# MCU_NODE.net
KiCad netlist of a schematic drawn in Altium Designer
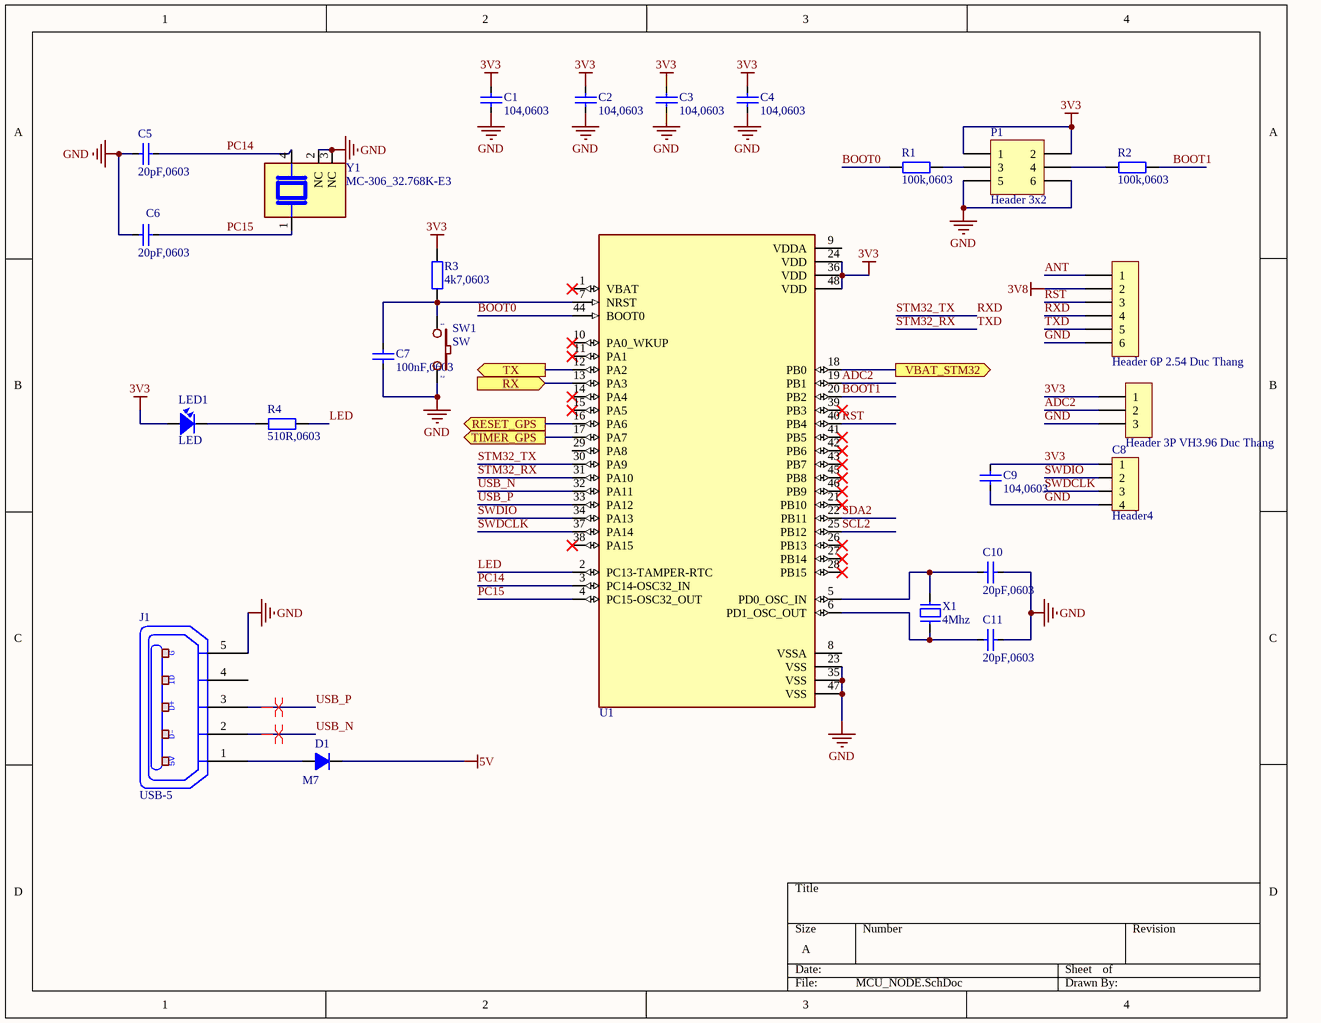
[diagram p0: MCU_NODE.SchDoc]

(export (version "E")
  (design (tool "Eeschema 10.0.6"))
  (components
    (comp (ref "C1")
      (value "104,0603")
      (footprint "CAP_0603")
      (description "Capacitor")
      (fields (field (name "PUBLISHER") "Altium Limited"))
      (libsource (lib "My Library") (part "CapSMD"))
    )
    (comp (ref "C2")
      (value "104,0603")
      (footprint "CAP_0603")
      (description "Capacitor")
      (fields (field (name "PUBLISHER") "Altium Limited"))
      (libsource (lib "My Library") (part "CapSMD"))
    )
    (comp (ref "C3")
      (value "104,0603")
      (footprint "CAP_0603")
      (description "Capacitor")
      (fields (field (name "PUBLISHER") "Altium Limited"))
      (libsource (lib "My Library") (part "CapSMD"))
    )
    (comp (ref "C4")
      (value "104,0603")
      (footprint "CAP_0603")
      (description "Capacitor")
      (fields (field (name "PUBLISHER") "Altium Limited"))
      (libsource (lib "My Library") (part "CapSMD"))
    )
    (comp (ref "C5")
      (value "20pF,0603")
      (footprint "CAP_0603")
      (description "Capacitor")
      (fields (field (name "PUBLISHER") "Altium Limited"))
      (libsource (lib "My Library") (part "CapSMD"))
    )
    (comp (ref "C6")
      (value "20pF,0603")
      (footprint "CAP_0603")
      (description "Capacitor")
      (fields (field (name "PUBLISHER") "Altium Limited"))
      (libsource (lib "My Library") (part "CapSMD"))
    )
    (comp (ref "C7")
      (value "100nF,0603")
      (footprint "CAP_0603")
      (description "Capacitor")
      (fields (field (name "PUBLISHER") "Altium Limited"))
      (libsource (lib "My Library") (part "CapSMD"))
    )
    (comp (ref "C8")
      (value "Header4")
      (footprint "JP4-D1C")
      (description "Header IDC, 4 x 1 Pin Vertical 2.54mm Pitch (Non-Boxed, Male)")
      (fields
        (field (name "MANUFACTURER") "Würth Elektronik eiSos GmbH")
        (field (name "PARTNO") "613002143121")
        (field (name "CREATED BY") "Karrer Zheng")
      )
      (libsource (lib "My Library") (part "Header4"))
    )
    (comp (ref "C9")
      (value "104,0603")
      (footprint "CAP_0603")
      (description "Capacitor")
      (fields (field (name "PUBLISHER") "Altium Limited"))
      (libsource (lib "My Library") (part "CapSMD"))
    )
    (comp (ref "C10")
      (value "20pF,0603")
      (footprint "CAP_0603")
      (description "Capacitor")
      (fields (field (name "PUBLISHER") "Altium Limited"))
      (libsource (lib "My Library") (part "CapSMD"))
    )
    (comp (ref "C11")
      (value "20pF,0603")
      (footprint "CAP_0603")
      (description "Capacitor")
      (fields (field (name "PUBLISHER") "Altium Limited"))
      (libsource (lib "My Library") (part "CapSMD"))
    )
    (comp (ref "D1")
      (value "M7")
      (footprint "SMA")
      (description "Diode 1A")
      (libsource (lib "Main") (part "D1A"))
    )
    (comp (ref "H1")
      (value "Header 6P 2.54 Duc Thang")
      (footprint "XH2.54M-6")
      (description "Cắm")
      (libsource (lib "Header") (part "Header 6P 2.54 Duc Thang"))
    )
    (comp (ref "H2")
      (value "Header 3P VH3.96 Duc Thang")
      (footprint "VH3.96M-3")
      (description "Cắm")
      (libsource (lib "Header") (part "Header 3P VH3.96 Duc Thang"))
    )
    (comp (ref "J1")
      (value "USB-5")
      (footprint "USB-M1")
      (fields
        (field (name "MANUFACTURER") "FCI")
        (field (name "MANUFACTURER PART NUMBER") "10118193-0001LF")
        (field (name ".CREATOR") "MM")
        (field (name ".CHECKED PCB") "RF")
        (field (name ".CHECKED SCH") "MM")
      )
      (libsource (lib "My Library") (part "USB-5"))
    )
    (comp (ref "LED1")
      (value "LED")
      (footprint "LED-0805-Blue")
      (description "LED Single colour Green and Red")
      (libsource (lib "My Library") (part "LED"))
    )
    (comp (ref "P1")
      (value "Header 3x2")
      (footprint "Header 3x2")
      (description "Header, 6-Pin, 2-Row")
      (fields (field (name "PUBLISHER") "Altium Limited"))
      (libsource (lib "hphonglib") (part "Header 3x2"))
    )
    (comp (ref "R1")
      (value "100k,0603")
      (footprint "RES-SMD-0603")
      (description "Resistor SMD")
      (fields
        (field (name "MANUFACTURER") "Generic Components")
        (field (name "PUBLISHER") "Altium Hobart Technology Centre")
      )
      (libsource (lib "My Library") (part "Resistor - SMD"))
    )
    (comp (ref "R2")
      (value "100k,0603")
      (footprint "RES-SMD-0603")
      (description "Resistor SMD")
      (fields
        (field (name "MANUFACTURER") "Generic Components")
        (field (name "PUBLISHER") "Altium Hobart Technology Centre")
      )
      (libsource (lib "My Library") (part "Resistor - SMD"))
    )
    (comp (ref "R3")
      (value "4k7,0603")
      (footprint "RES-SMD-0603")
      (description "Resistor SMD")
      (fields
        (field (name "MANUFACTURER") "Generic Components")
        (field (name "PUBLISHER") "Altium Hobart Technology Centre")
      )
      (libsource (lib "My Library") (part "Resistor - SMD"))
    )
    (comp (ref "R4")
      (value "510R,0603")
      (footprint "RES-SMD-0603")
      (description "Resistor SMD")
      (fields
        (field (name "MANUFACTURER") "Generic Components")
        (field (name "PUBLISHER") "Altium Hobart Technology Centre")
      )
      (libsource (lib "My Library") (part "Resistor - SMD"))
    )
    (comp (ref "SW1")
      (value "SW")
      (footprint "SW-SMD")
      (description "Switch button 2 pin")
      (libsource (lib "My Library") (part "SW2"))
    )
    (comp (ref "U1")
      (value "STM32")
      (footprint "LQFP 48")
      (description "STM32 ARM-based 32-bit MCU with 64 Kbytes Flash, 64-pin LQFP, Industrial Temperature")
      (libsource (lib "My Library") (part "STM32F103C8T6"))
    )
    (comp (ref "X1")
      (value "4Mhz")
      (footprint "XT2")
      (description "Crystal For all Crystal 2pin.")
      (libsource (lib "My Library") (part "XT2"))
    )
    (comp (ref "Y1")
      (value "MC-306_32.768K-E3")
      (footprint "XTAL_MC-306_32.768K-E3")
      (description "CRYSTAL 32.7680KHZ 6PF SMD")
      (fields (field (name "MF") "EPSON") (field (name "MP") "MC-306 32.768K-E3"))
      (libsource (lib "MC-306_32.768K-E3") (part "MC-306_32.768K-E3"))
    )
  )
  (nets
    (net (code "1") (name "/ADC2") (class "Default")
      (node (ref "H2") (pin "2") (pinfunction "2_2") (pintype "passive"))
      (node (ref "U1") (pin "19") (pinfunction "PB1_19") (pintype "bidirectional"))
    )
    (net (code "2") (name "/ANT") (class "Default")
      (node (ref "H1") (pin "1") (pinfunction "1_1") (pintype "passive"))
    )
    (net (code "3") (name "/BOOT0") (class "Default")
      (node (ref "R1") (pin "1") (pinfunction "1_1") (pintype "passive"))
      (node (ref "U1") (pin "44") (pinfunction "BOOT0_44") (pintype "input"))
    )
    (net (code "4") (name "/BOOT1") (class "Default")
      (node (ref "R2") (pin "2") (pinfunction "2_2") (pintype "passive"))
      (node (ref "U1") (pin "20") (pinfunction "PB2_20") (pintype "bidirectional"))
    )
    (net (code "5") (name "/LED") (class "Default")
      (node (ref "R4") (pin "2") (pinfunction "2_2") (pintype "passive"))
      (node (ref "U1") (pin "2") (pinfunction "PC13-TAMPER-RTC_2") (pintype "bidirectional"))
    )
    (net (code "6") (name "/PC14") (class "Default")
      (node (ref "C5") (pin "2") (pinfunction "2_2") (pintype "passive"))
      (node (ref "U1") (pin "3") (pinfunction "PC14-OSC32_IN_3") (pintype "bidirectional"))
      (node (ref "Y1") (pin "4") (pinfunction "2_4") (pintype "passive"))
    )
    (net (code "7") (name "/PC15") (class "Default")
      (node (ref "C6") (pin "2") (pinfunction "2_2") (pintype "passive"))
      (node (ref "U1") (pin "4") (pinfunction "PC15-OSC32_OUT_4") (pintype "bidirectional"))
      (node (ref "Y1") (pin "1") (pinfunction "1_1") (pintype "passive"))
    )
    (net (code "8") (name "/RESET_GPS") (class "Default")
      (node (ref "U1") (pin "16") (pinfunction "PA6_16") (pintype "bidirectional"))
    )
    (net (code "9") (name "/RST") (class "Default")
      (node (ref "H1") (pin "3") (pinfunction "3_3") (pintype "passive"))
      (node (ref "U1") (pin "40") (pinfunction "PB4_40") (pintype "bidirectional"))
    )
    (net (code "10") (name "/RX") (class "Default")
      (node (ref "U1") (pin "13") (pinfunction "PA3_13") (pintype "bidirectional"))
    )
    (net (code "11") (name "/RXD") (class "Default")
      (node (ref "H1") (pin "4") (pinfunction "4_4") (pintype "passive"))
      (node (ref "U1") (pin "30") (pinfunction "PA9_30") (pintype "bidirectional"))
    )
    (net (code "12") (name "/SCL2") (class "Default")
      (node (ref "U1") (pin "25") (pinfunction "PB12_25") (pintype "bidirectional"))
    )
    (net (code "13") (name "/SDA2") (class "Default")
      (node (ref "U1") (pin "22") (pinfunction "PB11_22") (pintype "bidirectional"))
    )
    (net (code "14") (name "/STM32_RX") (class "Default")
      (node (ref "H1") (pin "5") (pinfunction "5_5") (pintype "passive"))
      (node (ref "U1") (pin "31") (pinfunction "PA10_31") (pintype "bidirectional"))
    )
    (net (code "15") (name "/SWDCLK") (class "Default")
      (node (ref "C8") (pin "3") (pinfunction "3_3") (pintype "passive"))
      (node (ref "U1") (pin "37") (pinfunction "PA14_37") (pintype "bidirectional"))
    )
    (net (code "16") (name "/SWDIO") (class "Default")
      (node (ref "C8") (pin "2") (pinfunction "2_2") (pintype "passive"))
      (node (ref "U1") (pin "34") (pinfunction "PA13_34") (pintype "bidirectional"))
    )
    (net (code "17") (name "/TIMER_GPS") (class "Default")
      (node (ref "U1") (pin "17") (pinfunction "PA7_17") (pintype "bidirectional"))
    )
    (net (code "18") (name "/TX") (class "Default")
      (node (ref "U1") (pin "12") (pinfunction "PA2_12") (pintype "bidirectional"))
    )
    (net (code "19") (name "/USB_N") (class "Default")
      (node (ref "J1") (pin "2") (pinfunction "P2_2") (pintype "passive"))
      (node (ref "U1") (pin "32") (pinfunction "PA11_32") (pintype "bidirectional"))
    )
    (net (code "20") (name "/USB_P") (class "Default")
      (node (ref "J1") (pin "3") (pinfunction "P3_3") (pintype "passive"))
      (node (ref "U1") (pin "33") (pinfunction "PA12_33") (pintype "bidirectional"))
    )
    (net (code "21") (name "/VBAT_STM32") (class "Default")
      (node (ref "U1") (pin "18") (pinfunction "PB0_18") (pintype "bidirectional"))
    )
    (net (code "22") (name "3V3") (class "Default")
      (node (ref "C1") (pin "2") (pinfunction "2_2") (pintype "passive"))
      (node (ref "C2") (pin "2") (pinfunction "2_2") (pintype "passive"))
      (node (ref "C3") (pin "2") (pinfunction "2_2") (pintype "passive"))
      (node (ref "C4") (pin "2") (pinfunction "2_2") (pintype "passive"))
      (node (ref "C8") (pin "1") (pinfunction "1_1") (pintype "passive"))
      (node (ref "C9") (pin "2") (pinfunction "2_2") (pintype "passive"))
      (node (ref "H2") (pin "1") (pinfunction "1_1") (pintype "passive"))
      (node (ref "LED1") (pin "1") (pinfunction "1_1") (pintype "passive"))
      (node (ref "P1") (pin "1") (pinfunction "1_1") (pintype "passive"))
      (node (ref "P1") (pin "2") (pinfunction "2_2") (pintype "passive"))
      (node (ref "R3") (pin "1") (pinfunction "1_1") (pintype "passive"))
      (node (ref "U1") (pin "24") (pinfunction "VDD_24") (pintype "power_in"))
      (node (ref "U1") (pin "36") (pinfunction "VDD_36") (pintype "power_in"))
      (node (ref "U1") (pin "48") (pinfunction "VDD_48") (pintype "power_in"))
    )
    (net (code "23") (name "3V8") (class "Default")
      (node (ref "H1") (pin "2") (pinfunction "2_2") (pintype "passive"))
    )
    (net (code "24") (name "5V") (class "Default")
      (node (ref "D1") (pin "2") (pinfunction "K_2") (pintype "passive"))
    )
    (net (code "25") (name "GND") (class "Default")
      (node (ref "C1") (pin "1") (pinfunction "1_1") (pintype "passive"))
      (node (ref "C10") (pin "2") (pinfunction "2_2") (pintype "passive"))
      (node (ref "C11") (pin "2") (pinfunction "2_2") (pintype "passive"))
      (node (ref "C2") (pin "1") (pinfunction "1_1") (pintype "passive"))
      (node (ref "C3") (pin "1") (pinfunction "1_1") (pintype "passive"))
      (node (ref "C4") (pin "1") (pinfunction "1_1") (pintype "passive"))
      (node (ref "C5") (pin "1") (pinfunction "1_1") (pintype "passive"))
      (node (ref "C6") (pin "1") (pinfunction "1_1") (pintype "passive"))
      (node (ref "C7") (pin "1") (pinfunction "1_1") (pintype "passive"))
      (node (ref "C8") (pin "4") (pinfunction "4_4") (pintype "passive"))
      (node (ref "C9") (pin "1") (pinfunction "1_1") (pintype "passive"))
      (node (ref "H1") (pin "6") (pinfunction "6_6") (pintype "passive"))
      (node (ref "H2") (pin "3") (pinfunction "3_3") (pintype "passive"))
      (node (ref "J1") (pin "5") (pinfunction "P5_5") (pintype "passive"))
      (node (ref "P1") (pin "5") (pinfunction "5_5") (pintype "passive"))
      (node (ref "P1") (pin "6") (pinfunction "6_6") (pintype "passive"))
      (node (ref "SW1") (pin "2") (pinfunction "2_2") (pintype "passive"))
      (node (ref "U1") (pin "23") (pinfunction "VSS_23") (pintype "power_in"))
      (node (ref "U1") (pin "35") (pinfunction "VSS_35") (pintype "power_in"))
      (node (ref "U1") (pin "47") (pinfunction "VSS_47") (pintype "power_in"))
      (node (ref "Y1") (pin "2") (pinfunction "NC_2") (pintype "passive"))
      (node (ref "Y1") (pin "3") (pinfunction "NC_3") (pintype "passive"))
    )
    (net (code "26") (name "Net-(D1-A)") (class "Default")
      (node (ref "D1") (pin "1") (pinfunction "A_1") (pintype "passive"))
      (node (ref "J1") (pin "1") (pinfunction "P1_1") (pintype "passive"))
    )
    (net (code "27") (name "Net-(LED1-Pad2)") (class "Default")
      (node (ref "LED1") (pin "2") (pinfunction "2_2") (pintype "passive"))
      (node (ref "R4") (pin "1") (pinfunction "1_1") (pintype "passive"))
    )
    (net (code "28") (name "Net-(P1-Pad3)") (class "Default")
      (node (ref "P1") (pin "3") (pinfunction "3_3") (pintype "passive"))
      (node (ref "R1") (pin "2") (pinfunction "2_2") (pintype "passive"))
    )
    (net (code "29") (name "Net-(P1-Pad4)") (class "Default")
      (node (ref "P1") (pin "4") (pinfunction "4_4") (pintype "passive"))
      (node (ref "R2") (pin "1") (pinfunction "1_1") (pintype "passive"))
    )
    (net (code "30") (name "Net-(U1-NRST)") (class "Default")
      (node (ref "C7") (pin "2") (pinfunction "2_2") (pintype "passive"))
      (node (ref "R3") (pin "2") (pinfunction "2_2") (pintype "passive"))
      (node (ref "SW1") (pin "1") (pinfunction "1_1") (pintype "passive"))
      (node (ref "U1") (pin "7") (pinfunction "NRST_7") (pintype "input"))
    )
    (net (code "31") (name "Net-(U1-PD0_OSC_IN)") (class "Default")
      (node (ref "C10") (pin "1") (pinfunction "1_1") (pintype "passive"))
      (node (ref "U1") (pin "5") (pinfunction "PD0_OSC_IN_5") (pintype "bidirectional"))
      (node (ref "X1") (pin "2") (pinfunction "2_2") (pintype "passive"))
    )
    (net (code "32") (name "Net-(U1-PD1_OSC_OUT)") (class "Default")
      (node (ref "C11") (pin "1") (pinfunction "1_1") (pintype "passive"))
      (node (ref "U1") (pin "6") (pinfunction "PD1_OSC_OUT_6") (pintype "bidirectional"))
      (node (ref "X1") (pin "1") (pinfunction "1_1") (pintype "passive"))
    )
    (net (code "33") (name "unconnected-(J1-P4-Pad4)") (class "Default")
      (node (ref "J1") (pin "4") (pinfunction "P4_4") (pintype "passive"))
    )
    (net (code "34") (name "unconnected-(U1-PA0_WKUP-Pad10)") (class "Default")
      (node (ref "U1") (pin "10") (pinfunction "PA0_WKUP_10") (pintype "bidirectional+no_connect"))
    )
    (net (code "35") (name "unconnected-(U1-PA1-Pad11)") (class "Default")
      (node (ref "U1") (pin "11") (pinfunction "PA1_11") (pintype "bidirectional+no_connect"))
    )
    (net (code "36") (name "unconnected-(U1-PA4-Pad14)") (class "Default")
      (node (ref "U1") (pin "14") (pinfunction "PA4_14") (pintype "bidirectional+no_connect"))
    )
    (net (code "37") (name "unconnected-(U1-PA5-Pad15)") (class "Default")
      (node (ref "U1") (pin "15") (pinfunction "PA5_15") (pintype "bidirectional+no_connect"))
    )
    (net (code "38") (name "unconnected-(U1-PA8-Pad29)") (class "Default")
      (node (ref "U1") (pin "29") (pinfunction "PA8_29") (pintype "bidirectional"))
    )
    (net (code "39") (name "unconnected-(U1-PA15-Pad38)") (class "Default")
      (node (ref "U1") (pin "38") (pinfunction "PA15_38") (pintype "bidirectional+no_connect"))
    )
    (net (code "40") (name "unconnected-(U1-PB3-Pad39)") (class "Default")
      (node (ref "U1") (pin "39") (pinfunction "PB3_39") (pintype "bidirectional+no_connect"))
    )
    (net (code "41") (name "unconnected-(U1-PB5-Pad41)") (class "Default")
      (node (ref "U1") (pin "41") (pinfunction "PB5_41") (pintype "bidirectional+no_connect"))
    )
    (net (code "42") (name "unconnected-(U1-PB6-Pad42)") (class "Default")
      (node (ref "U1") (pin "42") (pinfunction "PB6_42") (pintype "bidirectional+no_connect"))
    )
    (net (code "43") (name "unconnected-(U1-PB7-Pad43)") (class "Default")
      (node (ref "U1") (pin "43") (pinfunction "PB7_43") (pintype "bidirectional+no_connect"))
    )
    (net (code "44") (name "unconnected-(U1-PB8-Pad45)") (class "Default")
      (node (ref "U1") (pin "45") (pinfunction "PB8_45") (pintype "bidirectional+no_connect"))
    )
    (net (code "45") (name "unconnected-(U1-PB9-Pad46)") (class "Default")
      (node (ref "U1") (pin "46") (pinfunction "PB9_46") (pintype "bidirectional+no_connect"))
    )
    (net (code "46") (name "unconnected-(U1-PB10-Pad21)") (class "Default")
      (node (ref "U1") (pin "21") (pinfunction "PB10_21") (pintype "bidirectional+no_connect"))
    )
    (net (code "47") (name "unconnected-(U1-PB13-Pad26)") (class "Default")
      (node (ref "U1") (pin "26") (pinfunction "PB13_26") (pintype "bidirectional+no_connect"))
    )
    (net (code "48") (name "unconnected-(U1-PB14-Pad27)") (class "Default")
      (node (ref "U1") (pin "27") (pinfunction "PB14_27") (pintype "bidirectional+no_connect"))
    )
    (net (code "49") (name "unconnected-(U1-PB15-Pad28)") (class "Default")
      (node (ref "U1") (pin "28") (pinfunction "PB15_28") (pintype "bidirectional+no_connect"))
    )
    (net (code "50") (name "unconnected-(U1-VBAT-Pad1)") (class "Default")
      (node (ref "U1") (pin "1") (pinfunction "VBAT_1") (pintype "bidirectional+no_connect"))
    )
    (net (code "51") (name "unconnected-(U1-VDDA-Pad9)") (class "Default")
      (node (ref "U1") (pin "9") (pinfunction "VDDA_9") (pintype "power_in"))
    )
    (net (code "52") (name "unconnected-(U1-VSSA-Pad8)") (class "Default")
      (node (ref "U1") (pin "8") (pinfunction "VSSA_8") (pintype "power_in"))
    )
  )
)
